# lego_air_quality.net
KiCad netlist of a schematic drawn in EAGLE
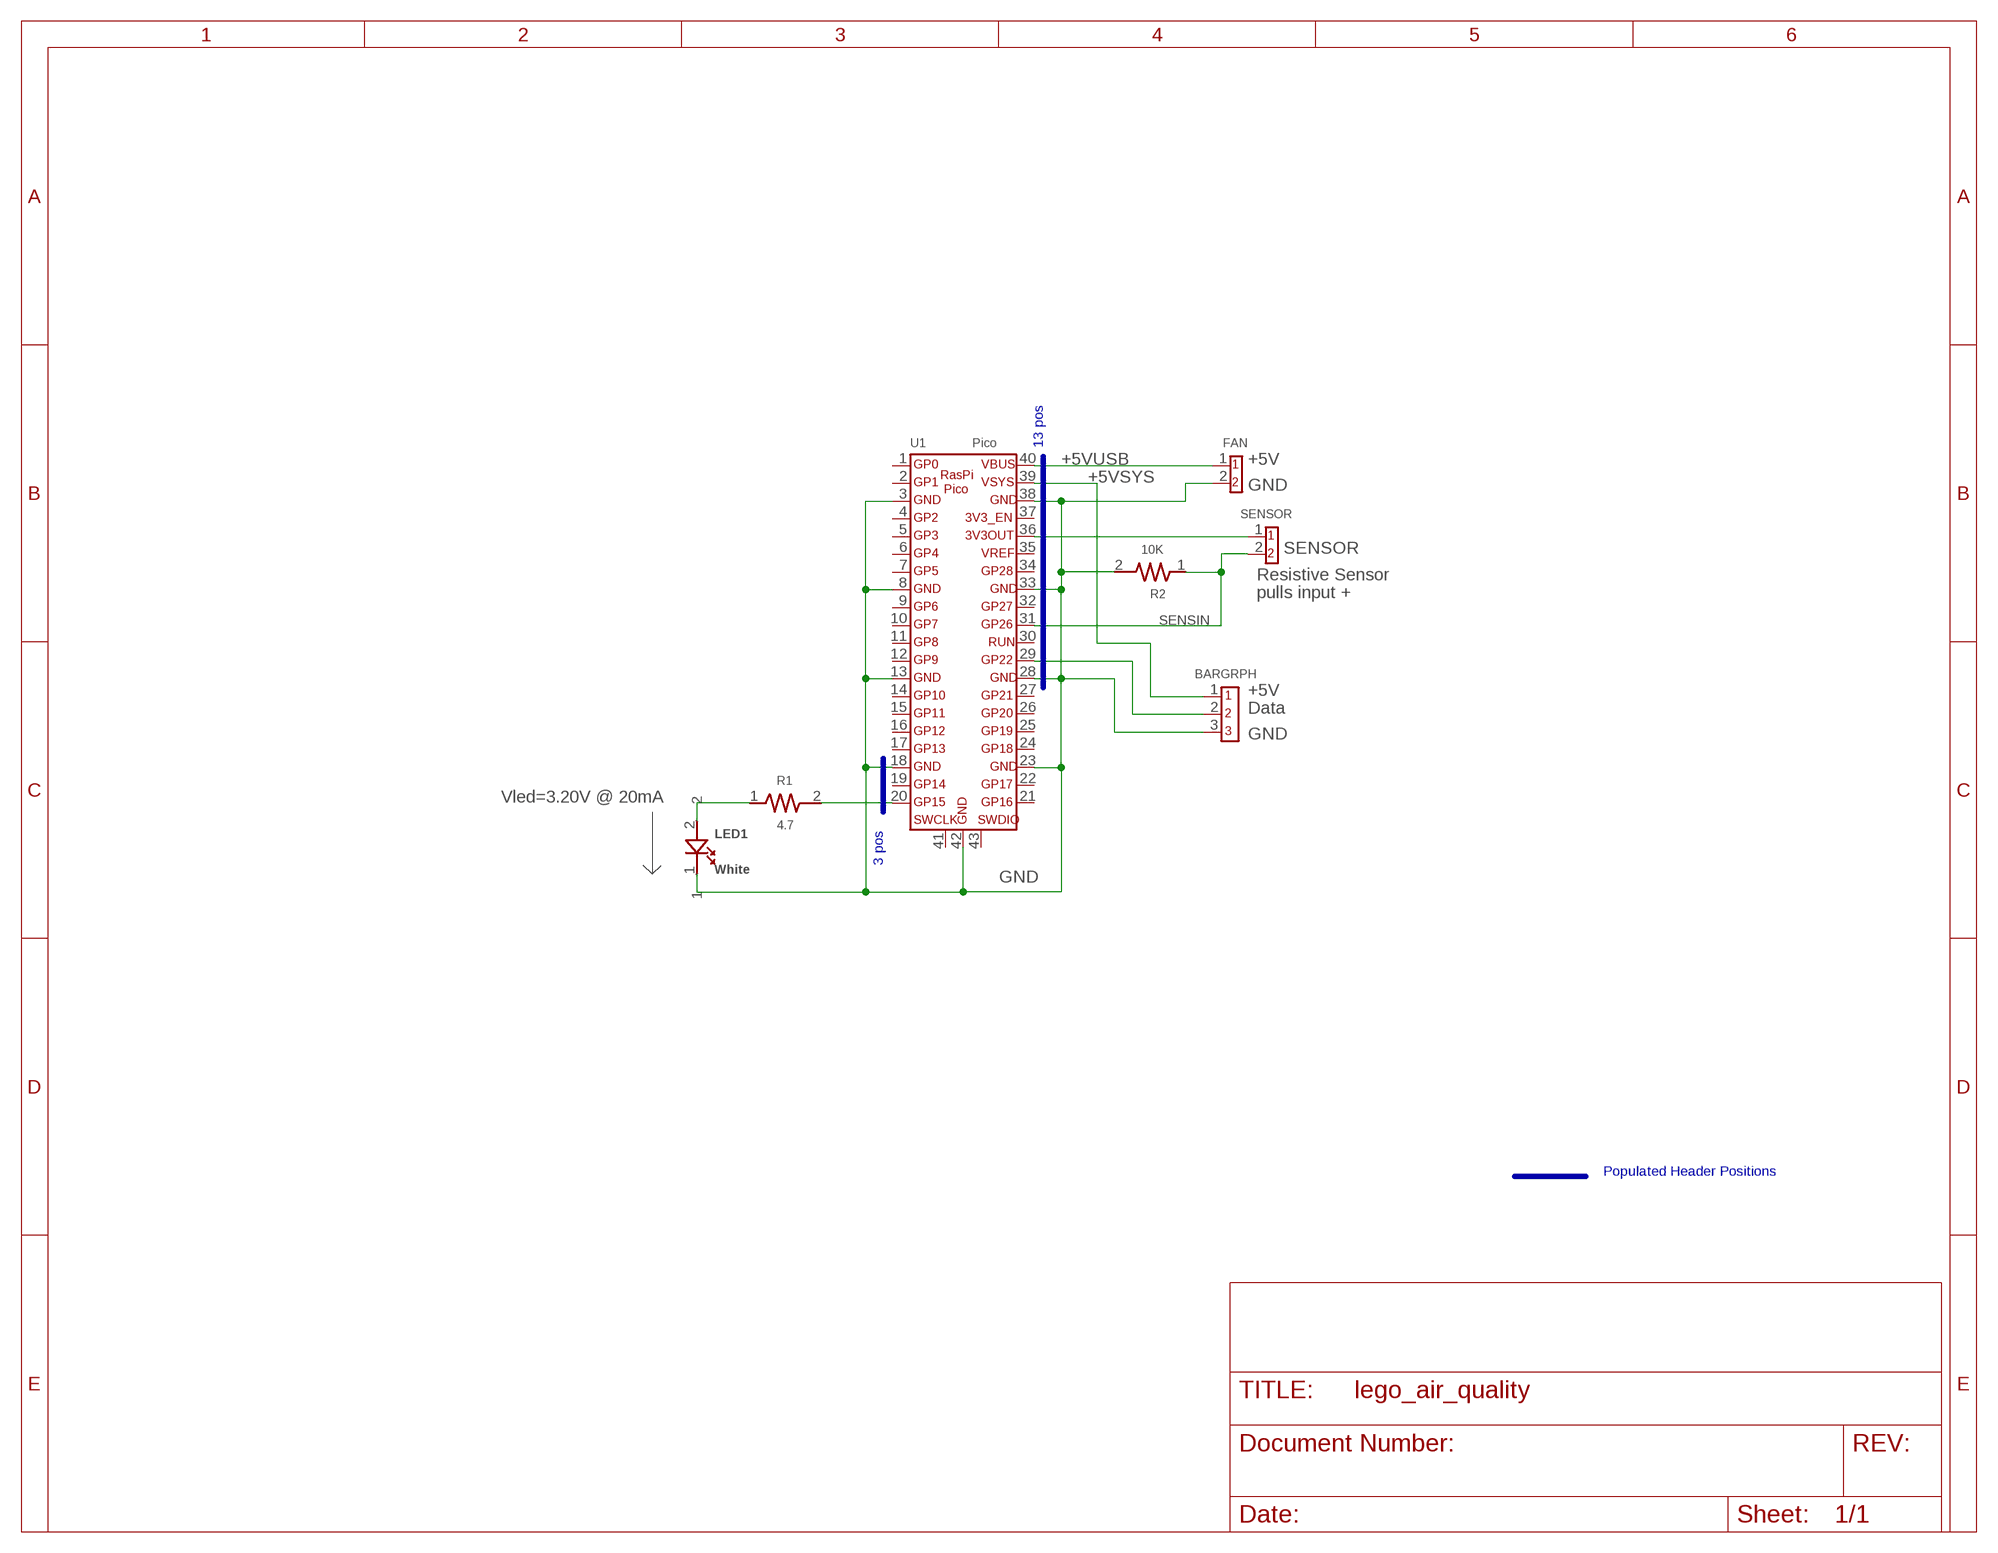
[diagram p0: schematic, sheet 1]

(export (version "E")
  (design (tool "Eeschema 10.0.6"))
  (components
    (comp (ref "BARGRPH")
      (value "3PINBERG")
      (footprint "eagle-import:3PINBERG")
      (libsource (lib "eagle-import") (part "3PINBERG"))
    )
    (comp (ref "FAN")
      (value "2PINBERG")
      (footprint "eagle-import:2PINBERG")
      (libsource (lib "eagle-import") (part "2PINBERG"))
    )
    (comp (ref "LED1")
      (value "White")
      (footprint "eagle-import:LED5MM")
      (libsource (lib "eagle-import") (part "LED5MM"))
    )
    (comp (ref "R1")
      (value "4.7")
      (footprint "eagle-import:R0_25W")
      (libsource (lib "eagle-import") (part "R0_25W"))
    )
    (comp (ref "R2")
      (value "10K")
      (footprint "eagle-import:R0_25W")
      (libsource (lib "eagle-import") (part "R0_25W"))
    )
    (comp (ref "SENSOR")
      (value "2PINBERG")
      (footprint "eagle-import:2PINBERG")
      (libsource (lib "eagle-import") (part "2PINBERG"))
    )
    (comp (ref "U1")
      (value "Pico")
      (footprint "eagle-import:RASPIPICO")
      (libsource (lib "eagle-import") (part "RASPIPICO"))
    )
  )
  (nets
    (net (code "1") (name "/+5VSYS") (class "Default")
      (node (ref "BARGRPH") (pin "1") (pinfunction "1_1") (pintype "bidirectional"))
      (node (ref "U1") (pin "39") (pinfunction "39_39") (pintype "bidirectional"))
    )
    (net (code "2") (name "/+5VUSB") (class "Default")
      (node (ref "FAN") (pin "1") (pinfunction "1_1") (pintype "bidirectional"))
      (node (ref "U1") (pin "40") (pinfunction "40_40") (pintype "bidirectional"))
    )
    (net (code "3") (name "/GND") (class "Default")
      (node (ref "BARGRPH") (pin "3") (pinfunction "3_3") (pintype "bidirectional"))
      (node (ref "FAN") (pin "2") (pinfunction "2_2") (pintype "bidirectional"))
      (node (ref "LED1") (pin "1") (pinfunction "1_1") (pintype "bidirectional"))
      (node (ref "R2") (pin "2") (pinfunction "2_2") (pintype "bidirectional"))
      (node (ref "U1") (pin "13") (pinfunction "13_13") (pintype "bidirectional"))
      (node (ref "U1") (pin "18") (pinfunction "18_18") (pintype "bidirectional"))
      (node (ref "U1") (pin "23") (pinfunction "23_23") (pintype "bidirectional"))
      (node (ref "U1") (pin "28") (pinfunction "28_28") (pintype "bidirectional"))
      (node (ref "U1") (pin "3") (pinfunction "3_3") (pintype "bidirectional"))
      (node (ref "U1") (pin "33") (pinfunction "33_33") (pintype "bidirectional"))
      (node (ref "U1") (pin "38") (pinfunction "38_38") (pintype "bidirectional"))
      (node (ref "U1") (pin "42") (pinfunction "42_42") (pintype "bidirectional"))
      (node (ref "U1") (pin "8") (pinfunction "8_8") (pintype "bidirectional"))
    )
    (net (code "4") (name "/SENSIN") (class "Default")
      (node (ref "R2") (pin "1") (pinfunction "1_1") (pintype "bidirectional"))
      (node (ref "SENSOR") (pin "2") (pinfunction "2_2") (pintype "bidirectional"))
      (node (ref "U1") (pin "31") (pinfunction "31_31") (pintype "bidirectional"))
    )
    (net (code "5") (name "Net-(BARGRPH-Pad2)") (class "Default")
      (node (ref "BARGRPH") (pin "2") (pinfunction "2_2") (pintype "bidirectional"))
      (node (ref "U1") (pin "29") (pinfunction "29_29") (pintype "bidirectional"))
    )
    (net (code "6") (name "Net-(LED1-Pad2)") (class "Default")
      (node (ref "LED1") (pin "2") (pinfunction "2_2") (pintype "bidirectional"))
      (node (ref "R1") (pin "1") (pinfunction "1_1") (pintype "bidirectional"))
    )
    (net (code "7") (name "Net-(R1-Pad2)") (class "Default")
      (node (ref "R1") (pin "2") (pinfunction "2_2") (pintype "bidirectional"))
      (node (ref "U1") (pin "20") (pinfunction "20_20") (pintype "bidirectional"))
    )
    (net (code "8") (name "Net-(SENSOR-Pad1)") (class "Default")
      (node (ref "SENSOR") (pin "1") (pinfunction "1_1") (pintype "bidirectional"))
      (node (ref "U1") (pin "36") (pinfunction "36_36") (pintype "bidirectional"))
    )
    (net (code "9") (name "unconnected-(U1-Pad1)") (class "Default")
      (node (ref "U1") (pin "1") (pinfunction "1_1") (pintype "bidirectional"))
    )
    (net (code "10") (name "unconnected-(U1-Pad2)") (class "Default")
      (node (ref "U1") (pin "2") (pinfunction "2_2") (pintype "bidirectional"))
    )
    (net (code "11") (name "unconnected-(U1-Pad4)") (class "Default")
      (node (ref "U1") (pin "4") (pinfunction "4_4") (pintype "bidirectional"))
    )
    (net (code "12") (name "unconnected-(U1-Pad5)") (class "Default")
      (node (ref "U1") (pin "5") (pinfunction "5_5") (pintype "bidirectional"))
    )
    (net (code "13") (name "unconnected-(U1-Pad6)") (class "Default")
      (node (ref "U1") (pin "6") (pinfunction "6_6") (pintype "bidirectional"))
    )
    (net (code "14") (name "unconnected-(U1-Pad7)") (class "Default")
      (node (ref "U1") (pin "7") (pinfunction "7_7") (pintype "bidirectional"))
    )
    (net (code "15") (name "unconnected-(U1-Pad9)") (class "Default")
      (node (ref "U1") (pin "9") (pinfunction "9_9") (pintype "bidirectional"))
    )
    (net (code "16") (name "unconnected-(U1-Pad10)") (class "Default")
      (node (ref "U1") (pin "10") (pinfunction "10_10") (pintype "bidirectional"))
    )
    (net (code "17") (name "unconnected-(U1-Pad11)") (class "Default")
      (node (ref "U1") (pin "11") (pinfunction "11_11") (pintype "bidirectional"))
    )
    (net (code "18") (name "unconnected-(U1-Pad12)") (class "Default")
      (node (ref "U1") (pin "12") (pinfunction "12_12") (pintype "bidirectional"))
    )
    (net (code "19") (name "unconnected-(U1-Pad14)") (class "Default")
      (node (ref "U1") (pin "14") (pinfunction "14_14") (pintype "bidirectional"))
    )
    (net (code "20") (name "unconnected-(U1-Pad15)") (class "Default")
      (node (ref "U1") (pin "15") (pinfunction "15_15") (pintype "bidirectional"))
    )
    (net (code "21") (name "unconnected-(U1-Pad16)") (class "Default")
      (node (ref "U1") (pin "16") (pinfunction "16_16") (pintype "bidirectional"))
    )
    (net (code "22") (name "unconnected-(U1-Pad17)") (class "Default")
      (node (ref "U1") (pin "17") (pinfunction "17_17") (pintype "bidirectional"))
    )
    (net (code "23") (name "unconnected-(U1-Pad19)") (class "Default")
      (node (ref "U1") (pin "19") (pinfunction "19_19") (pintype "bidirectional"))
    )
    (net (code "24") (name "unconnected-(U1-Pad21)") (class "Default")
      (node (ref "U1") (pin "21") (pinfunction "21_21") (pintype "bidirectional"))
    )
    (net (code "25") (name "unconnected-(U1-Pad22)") (class "Default")
      (node (ref "U1") (pin "22") (pinfunction "22_22") (pintype "bidirectional"))
    )
    (net (code "26") (name "unconnected-(U1-Pad24)") (class "Default")
      (node (ref "U1") (pin "24") (pinfunction "24_24") (pintype "bidirectional"))
    )
    (net (code "27") (name "unconnected-(U1-Pad25)") (class "Default")
      (node (ref "U1") (pin "25") (pinfunction "25_25") (pintype "bidirectional"))
    )
    (net (code "28") (name "unconnected-(U1-Pad26)") (class "Default")
      (node (ref "U1") (pin "26") (pinfunction "26_26") (pintype "bidirectional"))
    )
    (net (code "29") (name "unconnected-(U1-Pad27)") (class "Default")
      (node (ref "U1") (pin "27") (pinfunction "27_27") (pintype "bidirectional"))
    )
    (net (code "30") (name "unconnected-(U1-Pad30)") (class "Default")
      (node (ref "U1") (pin "30") (pinfunction "30_30") (pintype "bidirectional"))
    )
    (net (code "31") (name "unconnected-(U1-Pad32)") (class "Default")
      (node (ref "U1") (pin "32") (pinfunction "32_32") (pintype "bidirectional"))
    )
    (net (code "32") (name "unconnected-(U1-Pad34)") (class "Default")
      (node (ref "U1") (pin "34") (pinfunction "34_34") (pintype "bidirectional"))
    )
    (net (code "33") (name "unconnected-(U1-Pad35)") (class "Default")
      (node (ref "U1") (pin "35") (pinfunction "35_35") (pintype "bidirectional"))
    )
    (net (code "34") (name "unconnected-(U1-Pad37)") (class "Default")
      (node (ref "U1") (pin "37") (pinfunction "37_37") (pintype "bidirectional"))
    )
    (net (code "35") (name "unconnected-(U1-Pad41)") (class "Default")
      (node (ref "U1") (pin "41") (pinfunction "41_41") (pintype "bidirectional"))
    )
    (net (code "36") (name "unconnected-(U1-Pad43)") (class "Default")
      (node (ref "U1") (pin "43") (pinfunction "43_43") (pintype "bidirectional"))
    )
  )
)
